# node_simple.net
KiCad netlist of a schematic drawn in Altium Designer
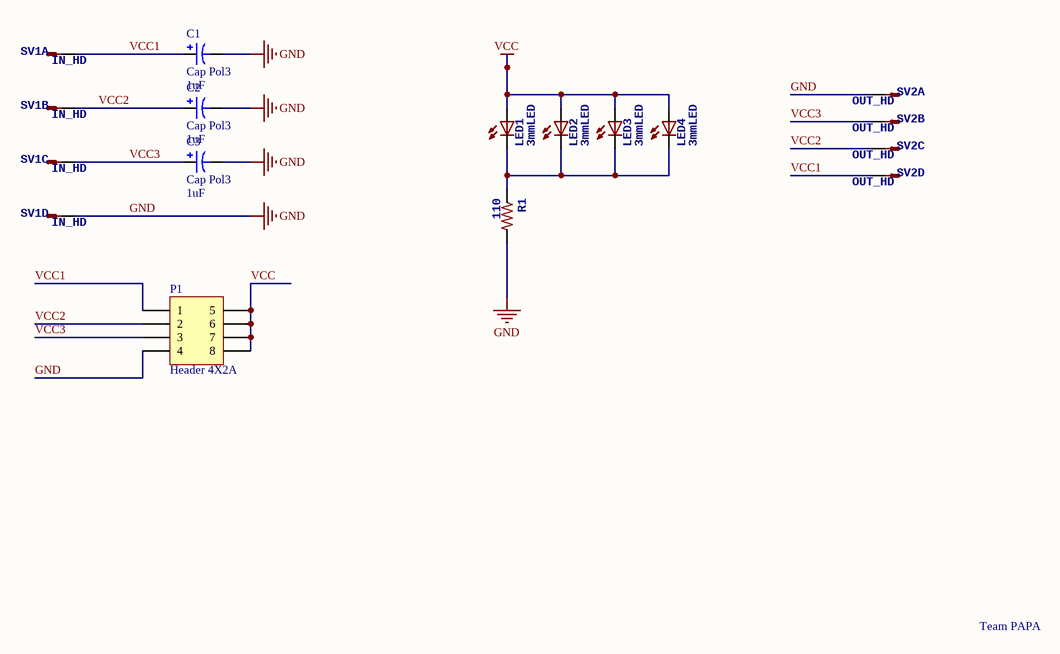
[diagram p0: node_simple.SchDoc]

(export (version "E")
  (design (tool "Eeschema 10.0.6"))
  (components
    (comp (ref "C1")
      (value "Cap Pol3")
      (footprint "C0805")
      (description "Polarized Capacitor (Surface Mount)")
      (fields (field (name "ALTIUM_VALUE") "1uF") (field (name "PUBLISHER") "Altium Limited"))
      (libsource (lib "Miscellaneous Devices") (part "Cap Pol3"))
    )
    (comp (ref "C2")
      (value "Cap Pol3")
      (footprint "C0805")
      (description "Polarized Capacitor (Surface Mount)")
      (fields (field (name "ALTIUM_VALUE") "1uF") (field (name "PUBLISHER") "Altium Limited"))
      (libsource (lib "Miscellaneous Devices") (part "Cap Pol3"))
    )
    (comp (ref "C3")
      (value "Cap Pol3")
      (footprint "C0805")
      (description "Polarized Capacitor (Surface Mount)")
      (fields (field (name "ALTIUM_VALUE") "1uF") (field (name "PUBLISHER") "Altium Limited"))
      (libsource (lib "Miscellaneous Devices") (part "Cap Pol3"))
    )
    (comp (ref "LED1") (value "3mmLED") (footprint "led3mm") (libsource (lib "adafruit") (part "LED3MM")))
    (comp (ref "LED2") (value "3mmLED") (footprint "led3mm") (libsource (lib "adafruit") (part "LED3MM")))
    (comp (ref "LED3") (value "3mmLED") (footprint "led3mm") (libsource (lib "adafruit") (part "LED3MM")))
    (comp (ref "LED4") (value "3mmLED") (footprint "led3mm") (libsource (lib "adafruit") (part "LED3MM")))
    (comp (ref "P1")
      (value "Header 4X2A")
      (footprint "HDR2X4_CEN")
      (description "Header, 4-Pin, Dual row")
      (fields (field (name "PUBLISHER") "Altium Limited"))
      (libsource (lib "Miscellaneous Connectors") (part "Header 4X2A"))
    )
    (comp (ref "R1")
      (value "110")
      (footprint "M0805")
      (description "R-M0805")
      (libsource (lib "adafruit") (part "R-US_M0805"))
    )
    (comp (ref "SV1") (value "IN_HD") (footprint "L04P") (libsource (lib "con-amp-mt") (part "L04P")))
    (comp (ref "SV2") (value "OUT_HD") (footprint "L04P") (libsource (lib "con-amp-mt") (part "L04P")))
  )
  (nets
    (net (code "1") (name "/VCC1") (class "Default")
      (node (ref "C1") (pin "1") (pinfunction "1_1") (pintype "passive"))
      (node (ref "P1") (pin "1") (pinfunction "1_1") (pintype "passive"))
      (node (ref "SV1") (pin "1") (pinfunction "S_1") (pintype "passive"))
      (node (ref "SV2") (pin "4") (pinfunction "S_4") (pintype "passive"))
    )
    (net (code "2") (name "/VCC2") (class "Default")
      (node (ref "C2") (pin "1") (pinfunction "1_1") (pintype "passive"))
      (node (ref "P1") (pin "2") (pinfunction "2_2") (pintype "passive"))
      (node (ref "SV1") (pin "2") (pinfunction "S_2") (pintype "passive"))
      (node (ref "SV2") (pin "3") (pinfunction "S_3") (pintype "passive"))
    )
    (net (code "3") (name "/VCC3") (class "Default")
      (node (ref "C3") (pin "1") (pinfunction "1_1") (pintype "passive"))
      (node (ref "P1") (pin "3") (pinfunction "3_3") (pintype "passive"))
      (node (ref "SV1") (pin "3") (pinfunction "S_3") (pintype "passive"))
      (node (ref "SV2") (pin "2") (pinfunction "S_2") (pintype "passive"))
    )
    (net (code "4") (name "GND") (class "Default")
      (node (ref "C1") (pin "2") (pinfunction "2_2") (pintype "passive"))
      (node (ref "C2") (pin "2") (pinfunction "2_2") (pintype "passive"))
      (node (ref "C3") (pin "2") (pinfunction "2_2") (pintype "passive"))
      (node (ref "P1") (pin "4") (pinfunction "4_4") (pintype "passive"))
      (node (ref "R1") (pin "2") (pinfunction "2_2") (pintype "passive"))
      (node (ref "SV1") (pin "4") (pinfunction "S_4") (pintype "passive"))
      (node (ref "SV2") (pin "1") (pinfunction "S_1") (pintype "passive"))
    )
    (net (code "5") (name "Net-(LED1-C)") (class "Default")
      (node (ref "LED1") (pin "K") (pinfunction "C_K") (pintype "passive"))
      (node (ref "LED2") (pin "K") (pinfunction "C_K") (pintype "passive"))
      (node (ref "LED3") (pin "K") (pinfunction "C_K") (pintype "passive"))
      (node (ref "LED4") (pin "K") (pinfunction "C_K") (pintype "passive"))
      (node (ref "R1") (pin "1") (pinfunction "1_1") (pintype "passive"))
    )
    (net (code "6") (name "VCC") (class "Default")
      (node (ref "LED1") (pin "A") (pinfunction "A_A") (pintype "passive"))
      (node (ref "LED2") (pin "A") (pinfunction "A_A") (pintype "passive"))
      (node (ref "LED3") (pin "A") (pinfunction "A_A") (pintype "passive"))
      (node (ref "LED4") (pin "A") (pinfunction "A_A") (pintype "passive"))
      (node (ref "P1") (pin "5") (pinfunction "5_5") (pintype "passive"))
      (node (ref "P1") (pin "6") (pinfunction "6_6") (pintype "passive"))
      (node (ref "P1") (pin "7") (pinfunction "7_7") (pintype "passive"))
      (node (ref "P1") (pin "8") (pinfunction "8_8") (pintype "passive"))
    )
  )
)
